# MP1477H_DCDC_5V.net
KiCad netlist of a schematic drawn in Altium Designer
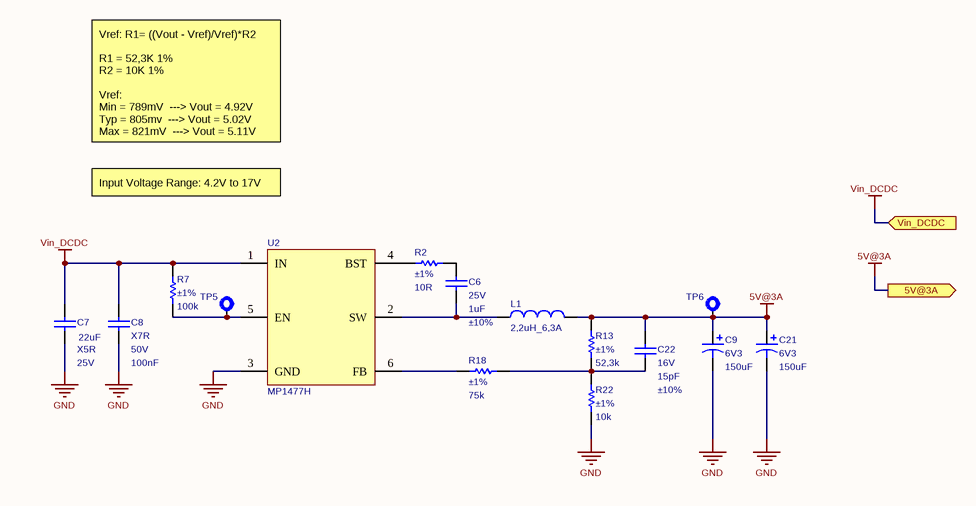
[diagram p0: MP1477H_DCDC_5V.SchDoc]

(export (version "E")
  (design (tool "Eeschema 10.0.6"))
  (components
    (comp (ref "C6")
      (value "C0603_1uF_25V_±10%")
      (footprint "C0603")
      (fields
        (field (name "VOLTAGE") "25V")
        (field (name "CAPACITANCE") "1uF")
        (field (name "TOLERANCE") "±10%")
        (field (name "MANUFACTURER") "Kemet")
      )
      (libsource (lib "BQ Vault") (part "Capacitor"))
    )
    (comp (ref "C7")
      (value "C1206_22uF_25V_±10%")
      (footprint "C1206")
      (fields
        (field (name "DIELECTRIC") "X5R")
        (field (name "VOLTAGE") "25V")
        (field (name "CAPACITANCE") "22uF")
        (field (name "TOLERANCE") "±10%")
        (field (name "MANUFACTURER") "Murata")
      )
      (libsource (lib "BQ Vault") (part "CMP-A0110-1"))
    )
    (comp (ref "C8")
      (value "C0603_100nF_50V_±10%_X7R")
      (footprint "C0603")
      (fields
        (field (name "DIELECTRIC") "X7R")
        (field (name "VOLTAGE") "50V")
        (field (name "CAPACITANCE") "100nF")
        (field (name "MANUFACTURER") "Kemet")
        (field (name "TOLERANCE") "±10%")
      )
      (libsource (lib "BQ Vault") (part "CMP-00257-1"))
    )
    (comp (ref "C9")
      (value "150uF_6V3_±20%")
      (footprint "CASE_B_3528-1411")
      (fields
        (field (name "VOLTAGE") "6V3")
        (field (name "CAPACITANCE") "150uF")
        (field (name "TOLERANCE") "±20%")
        (field (name "MANUFACTURER") "Kemet")
      )
      (libsource (lib "BQ Vault") (part "Tantalum"))
    )
    (comp (ref "C21")
      (value "150uF_6V3_±20%")
      (footprint "CASE_B_3528-1411")
      (fields
        (field (name "VOLTAGE") "6V3")
        (field (name "CAPACITANCE") "150uF")
        (field (name "TOLERANCE") "±20%")
        (field (name "MANUFACTURER") "Kemet")
      )
      (libsource (lib "BQ Vault") (part "Tantalum"))
    )
    (comp (ref "C22")
      (value "C0402_15pF_16V_±10%_C0G")
      (footprint "C0402")
      (fields
        (field (name "VOLTAGE") "16V")
        (field (name "CAPACITANCE") "15pF")
        (field (name "PART NUMBER") "C0402_15pF_16V_±10%")
        (field (name "TOLERANCE") "±10%")
        (field (name "MANUFACTURER") "Kemet")
      )
      (libsource (lib "BQ Vault") (part "Capacitor"))
    )
    (comp (ref "L1")
      (value "2,2uH_6,3A")
      (footprint "SRN8040")
      (description "Semi-shielded power inductor")
      (fields (field (name "MANUFACTURER") "Bourns"))
      (libsource (lib "BQ Vault") (part "Inductor"))
    )
    (comp (ref "R2")
      (value "R0402_10R_0.063W_±1%")
      (footprint "R0402")
      (fields
        (field (name "TOLERANCE") "±1%")
        (field (name "POWER") "0.063W")
        (field (name "RESISTANCE") "10R")
        (field (name "MANUFACTURER") "Vishay")
      )
      (libsource (lib "BQ Vault") (part "Resistor"))
    )
    (comp (ref "R7")
      (value "R0402_100k_0.063W_±1%")
      (footprint "R0402")
      (fields
        (field (name "TOLERANCE") "±1%")
        (field (name "POWER") "0.063W")
        (field (name "RESISTANCE") "100k")
        (field (name "MANUFACTURER") "Vishay")
      )
      (libsource (lib "BQ Vault") (part "Resistor"))
    )
    (comp (ref "R13")
      (value "R0402_52,3k_0.063W_±1%")
      (footprint "R0402")
      (fields
        (field (name "TOLERANCE") "±1%")
        (field (name "POWER") "0.063W")
        (field (name "RESISTANCE") "52,3k")
        (field (name "MANUFACTURER") "Vishay")
      )
      (libsource (lib "BQ Vault") (part "Resistor"))
    )
    (comp (ref "R18")
      (value "R0402_75k_0.063W_±1%")
      (footprint "R0402")
      (fields
        (field (name "TOLERANCE") "±1%")
        (field (name "POWER") "0.063W")
        (field (name "RESISTANCE") "75k")
        (field (name "MANUFACTURER") "Vishay")
      )
      (libsource (lib "BQ Vault") (part "Resistor"))
    )
    (comp (ref "R22")
      (value "R0402_10k_0.063W_±1%")
      (footprint "R0402")
      (fields
        (field (name "TOLERANCE") "±1%")
        (field (name "POWER") "0.063W")
        (field (name "RESISTANCE") "10k")
        (field (name "MANUFACTURER") "Vishay")
      )
      (libsource (lib "BQ Vault") (part "Resistor"))
    )
    (comp (ref "TP5")
      (value "TP")
      (footprint "TP_POWER")
      (description "Testpoint 0.3mm")
      (fields (field (name "MANUFACTURER") "Oxley") (field (name "PART NUMBER") "TP_POWER"))
      (libsource (lib "BQ Vault") (part "CMP-A2499-3"))
    )
    (comp (ref "TP6")
      (value "TP")
      (footprint "TP_POWER")
      (description "Testpoint 0.3mm")
      (fields (field (name "MANUFACTURER") "Oxley") (field (name "PART NUMBER") "TP_POWER"))
      (libsource (lib "BQ Vault") (part "CMP-A2499-3"))
    )
    (comp (ref "U2")
      (value "MP1477H")
      (footprint "SOT-563 - MP1477H")
      (description "DCDC Step Down Vout= 1-5V; Vin= 12-17V")
      (fields (field (name "MANUFACTURER") "MPS") (field (name "PART NUMBER") "MP1477GTF-Z"))
      (libsource (lib "BQ Vault") (part "CMP-00385-3"))
    )
  )
  (nets
    (net (code "1") (name "5V@3A") (class "Default")
      (node (ref "C21") (pin "1") (pinfunction "1_1") (pintype "passive"))
      (node (ref "C22") (pin "2") (pinfunction "2_2") (pintype "passive"))
      (node (ref "C9") (pin "1") (pinfunction "1_1") (pintype "passive"))
      (node (ref "L1") (pin "2") (pinfunction "2_2") (pintype "passive"))
      (node (ref "R13") (pin "1") (pinfunction "1_1") (pintype "passive"))
      (node (ref "TP6") (pin "1") (pinfunction "1_1") (pintype "passive"))
    )
    (net (code "2") (name "GND") (class "Default")
      (node (ref "C21") (pin "2") (pinfunction "2_2") (pintype "passive"))
      (node (ref "C7") (pin "1") (pinfunction "1_1") (pintype "passive"))
      (node (ref "C8") (pin "1") (pinfunction "1_1") (pintype "passive"))
      (node (ref "C9") (pin "2") (pinfunction "2_2") (pintype "passive"))
      (node (ref "R22") (pin "2") (pinfunction "2_2") (pintype "passive"))
      (node (ref "U2") (pin "3") (pinfunction "GND_3") (pintype "passive"))
    )
    (net (code "3") (name "Net-(C6-Pad2)") (class "Default")
      (node (ref "C6") (pin "2") (pinfunction "2_2") (pintype "passive"))
      (node (ref "R2") (pin "2") (pinfunction "2_2") (pintype "passive"))
    )
    (net (code "4") (name "Net-(C22-Pad1)") (class "Default")
      (node (ref "C22") (pin "1") (pinfunction "1_1") (pintype "passive"))
      (node (ref "R13") (pin "2") (pinfunction "2_2") (pintype "passive"))
      (node (ref "R18") (pin "2") (pinfunction "2_2") (pintype "passive"))
      (node (ref "R22") (pin "1") (pinfunction "1_1") (pintype "passive"))
    )
    (net (code "5") (name "Net-(U2-BST)") (class "Default")
      (node (ref "R2") (pin "1") (pinfunction "1_1") (pintype "passive"))
      (node (ref "U2") (pin "4") (pinfunction "BST_4") (pintype "passive"))
    )
    (net (code "6") (name "Net-(U2-EN)") (class "Default")
      (node (ref "R7") (pin "1") (pinfunction "1_1") (pintype "passive"))
      (node (ref "TP5") (pin "1") (pinfunction "1_1") (pintype "passive"))
      (node (ref "U2") (pin "5") (pinfunction "EN_5") (pintype "passive"))
    )
    (net (code "7") (name "Net-(U2-FB)") (class "Default")
      (node (ref "R18") (pin "1") (pinfunction "1_1") (pintype "passive"))
      (node (ref "U2") (pin "6") (pinfunction "FB_6") (pintype "passive"))
    )
    (net (code "8") (name "Net-(U2-SW)") (class "Default")
      (node (ref "C6") (pin "1") (pinfunction "1_1") (pintype "passive"))
      (node (ref "L1") (pin "1") (pinfunction "1_1") (pintype "passive"))
      (node (ref "U2") (pin "2") (pinfunction "SW_2") (pintype "passive"))
    )
    (net (code "9") (name "Vin_DCDC") (class "Default")
      (node (ref "C7") (pin "2") (pinfunction "2_2") (pintype "passive"))
      (node (ref "C8") (pin "2") (pinfunction "2_2") (pintype "passive"))
      (node (ref "R7") (pin "2") (pinfunction "2_2") (pintype "passive"))
      (node (ref "U2") (pin "1") (pinfunction "IN_1") (pintype "passive"))
    )
  )
)
